# Preamp_board1.net
KiCad netlist of a schematic drawn in EAGLE
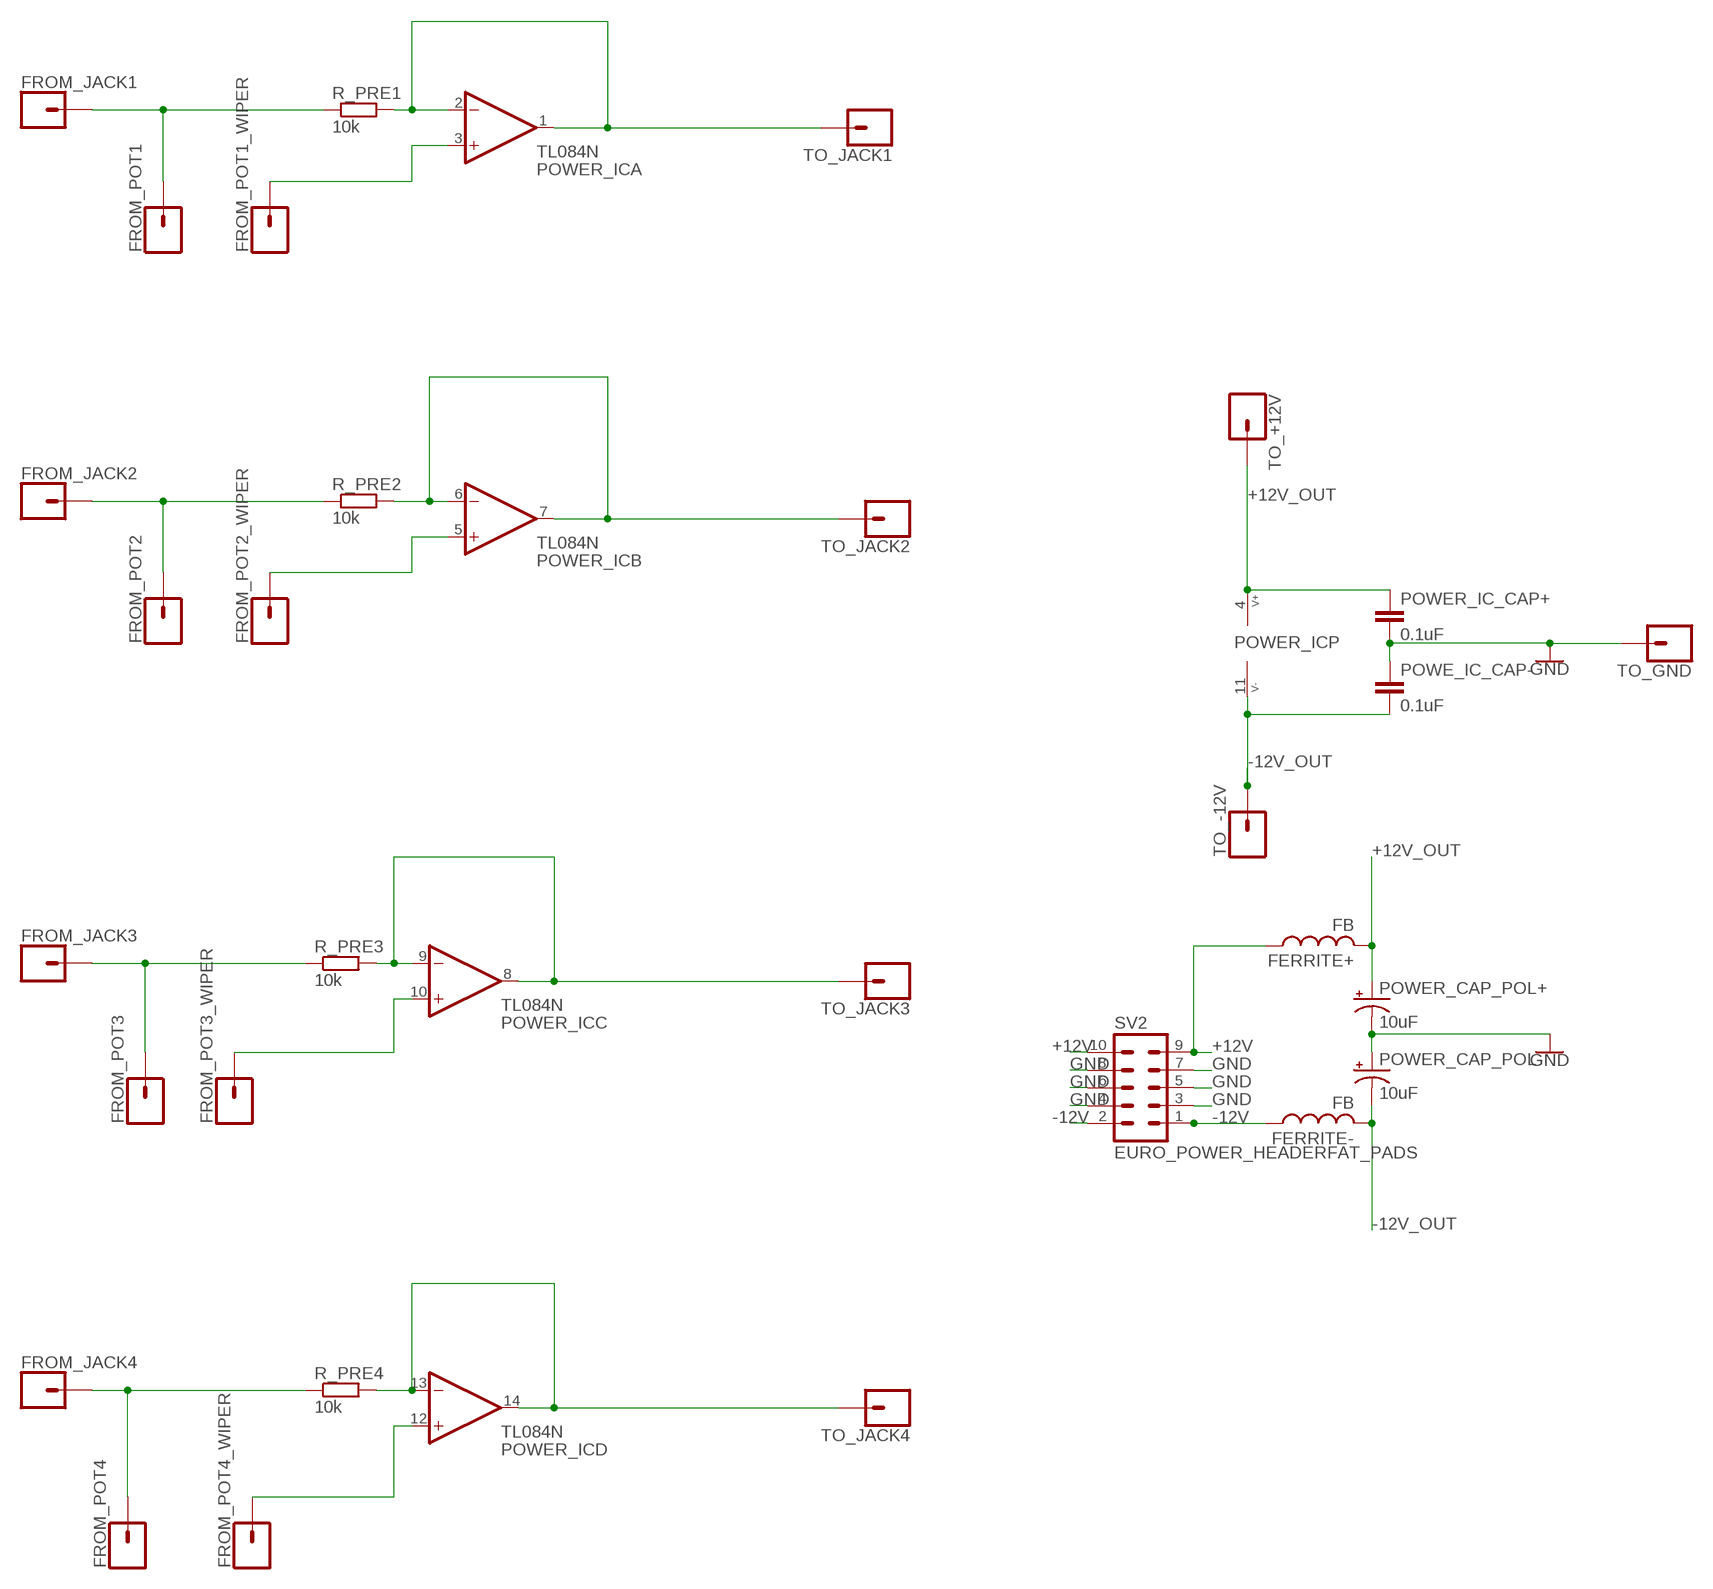
[diagram p0: schematic, sheet 1]

(export (version "E")
  (design (tool "Eeschema 10.0.6"))
  (components
    (comp (ref "FERRITE+")
      (value "FB")
      (footprint "eagle-import:FB")
      (libsource (lib "eagle-import") (part "FB"))
    )
    (comp (ref "FERRITE-")
      (value "FB")
      (footprint "eagle-import:FB")
      (libsource (lib "eagle-import") (part "FB"))
    )
    (comp (ref "FROM_JACK1")
      (value "CONN_01PTH_LONGPAD")
      (footprint "eagle-import:1X01_LONGPAD")
      (libsource (lib "eagle-import") (part "CONN_01PTH_LONGPAD"))
    )
    (comp (ref "FROM_JACK2")
      (value "CONN_01PTH_LONGPAD")
      (footprint "eagle-import:1X01_LONGPAD")
      (libsource (lib "eagle-import") (part "CONN_01PTH_LONGPAD"))
    )
    (comp (ref "FROM_JACK3")
      (value "CONN_01PTH_LONGPAD")
      (footprint "eagle-import:1X01_LONGPAD")
      (libsource (lib "eagle-import") (part "CONN_01PTH_LONGPAD"))
    )
    (comp (ref "FROM_JACK4")
      (value "CONN_01PTH_LONGPAD")
      (footprint "eagle-import:1X01_LONGPAD")
      (libsource (lib "eagle-import") (part "CONN_01PTH_LONGPAD"))
    )
    (comp (ref "FROM_POT1")
      (value "CONN_01PTH_LONGPAD")
      (footprint "eagle-import:1X01_LONGPAD")
      (libsource (lib "eagle-import") (part "CONN_01PTH_LONGPAD"))
    )
    (comp (ref "FROM_POT1_WIPER")
      (value "CONN_01PTH_LONGPAD")
      (footprint "eagle-import:1X01_LONGPAD")
      (libsource (lib "eagle-import") (part "CONN_01PTH_LONGPAD"))
    )
    (comp (ref "FROM_POT2")
      (value "CONN_01PTH_LONGPAD")
      (footprint "eagle-import:1X01_LONGPAD")
      (libsource (lib "eagle-import") (part "CONN_01PTH_LONGPAD"))
    )
    (comp (ref "FROM_POT2_WIPER")
      (value "CONN_01PTH_LONGPAD")
      (footprint "eagle-import:1X01_LONGPAD")
      (libsource (lib "eagle-import") (part "CONN_01PTH_LONGPAD"))
    )
    (comp (ref "FROM_POT3")
      (value "CONN_01PTH_LONGPAD")
      (footprint "eagle-import:1X01_LONGPAD")
      (libsource (lib "eagle-import") (part "CONN_01PTH_LONGPAD"))
    )
    (comp (ref "FROM_POT3_WIPER")
      (value "CONN_01PTH_LONGPAD")
      (footprint "eagle-import:1X01_LONGPAD")
      (libsource (lib "eagle-import") (part "CONN_01PTH_LONGPAD"))
    )
    (comp (ref "FROM_POT4")
      (value "CONN_01PTH_LONGPAD")
      (footprint "eagle-import:1X01_LONGPAD")
      (libsource (lib "eagle-import") (part "CONN_01PTH_LONGPAD"))
    )
    (comp (ref "FROM_POT4_WIPER")
      (value "CONN_01PTH_LONGPAD")
      (footprint "eagle-import:1X01_LONGPAD")
      (libsource (lib "eagle-import") (part "CONN_01PTH_LONGPAD"))
    )
    (comp (ref "POWER_CAP_POL+")
      (value "10uF")
      (footprint "eagle-import:CPOL-RADIAL-2.5MM-5MM")
      (libsource (lib "eagle-import") (part "10UF-POLAR-RADIAL-2.5MM-25V-20%"))
    )
    (comp (ref "POWER_CAP_POL-")
      (value "10uF")
      (footprint "eagle-import:CPOL-RADIAL-2.5MM-5MM")
      (libsource (lib "eagle-import") (part "10UF-POLAR-RADIAL-2.5MM-25V-20%"))
    )
    (comp (ref "POWER_IC")
      (value "TL084N")
      (footprint "eagle-import:DIL14")
      (libsource (lib "eagle-import") (part "TL084N"))
    )
    (comp (ref "POWER_IC_CAP+")
      (value "0.1uF")
      (footprint "eagle-import:CAP-PTH-SMALL-KIT")
      (libsource (lib "eagle-import") (part "0.1UF-KIT-EZ-50V-20%"))
    )
    (comp (ref "POWE_IC_CAP-")
      (value "0.1uF")
      (footprint "eagle-import:CAP-PTH-SMALL-KIT")
      (libsource (lib "eagle-import") (part "0.1UF-KIT-EZ-50V-20%"))
    )
    (comp (ref "R_PRE1")
      (value "10k")
      (footprint "eagle-import:7MM_RESISTOR")
      (libsource (lib "eagle-import") (part "RESISTOR7MM"))
    )
    (comp (ref "R_PRE2")
      (value "10k")
      (footprint "eagle-import:7MM_RESISTOR")
      (libsource (lib "eagle-import") (part "RESISTOR7MM"))
    )
    (comp (ref "R_PRE3")
      (value "10k")
      (footprint "eagle-import:7MM_RESISTOR")
      (libsource (lib "eagle-import") (part "RESISTOR7MM"))
    )
    (comp (ref "R_PRE4")
      (value "10k")
      (footprint "eagle-import:7MM_RESISTOR")
      (libsource (lib "eagle-import") (part "RESISTOR7MM"))
    )
    (comp (ref "SV2")
      (value "EURO_POWER_HEADERFAT_PADS")
      (footprint "eagle-import:EURO_PWR_HEADER_FAT")
      (libsource (lib "eagle-import") (part "EURO_POWER_HEADERFAT_PADS"))
    )
    (comp (ref "TO_+12V")
      (value "CONN_01PTH_LONGPAD")
      (footprint "eagle-import:1X01_LONGPAD")
      (libsource (lib "eagle-import") (part "CONN_01PTH_LONGPAD"))
    )
    (comp (ref "TO_-12V")
      (value "CONN_01PTH_LONGPAD")
      (footprint "eagle-import:1X01_LONGPAD")
      (libsource (lib "eagle-import") (part "CONN_01PTH_LONGPAD"))
    )
    (comp (ref "TO_GND")
      (value "CONN_01PTH_LONGPAD")
      (footprint "eagle-import:1X01_LONGPAD")
      (libsource (lib "eagle-import") (part "CONN_01PTH_LONGPAD"))
    )
    (comp (ref "TO_JACK1")
      (value "CONN_01PTH_LONGPAD")
      (footprint "eagle-import:1X01_LONGPAD")
      (libsource (lib "eagle-import") (part "CONN_01PTH_LONGPAD"))
    )
    (comp (ref "TO_JACK2")
      (value "CONN_01PTH_LONGPAD")
      (footprint "eagle-import:1X01_LONGPAD")
      (libsource (lib "eagle-import") (part "CONN_01PTH_LONGPAD"))
    )
    (comp (ref "TO_JACK3")
      (value "CONN_01PTH_LONGPAD")
      (footprint "eagle-import:1X01_LONGPAD")
      (libsource (lib "eagle-import") (part "CONN_01PTH_LONGPAD"))
    )
    (comp (ref "TO_JACK4")
      (value "CONN_01PTH_LONGPAD")
      (footprint "eagle-import:1X01_LONGPAD")
      (libsource (lib "eagle-import") (part "CONN_01PTH_LONGPAD"))
    )
  )
  (nets
    (net (code "1") (name "/+12V") (class "Default")
      (node (ref "FERRITE+") (pin "P$1") (pinfunction "1_P$1") (pintype "passive"))
      (node (ref "SV2") (pin "10") (pinfunction "10_10") (pintype "passive"))
      (node (ref "SV2") (pin "9") (pinfunction "9_9") (pintype "passive"))
    )
    (net (code "2") (name "/+12V_OUT") (class "Default")
      (node (ref "FERRITE+") (pin "P$2") (pinfunction "2_P$2") (pintype "passive"))
      (node (ref "POWER_CAP_POL+") (pin "1") (pinfunction "+_1") (pintype "passive"))
      (node (ref "POWER_IC") (pin "4") (pinfunction "V+_4") (pintype "power_in"))
      (node (ref "POWER_IC_CAP+") (pin "1") (pinfunction "1_1") (pintype "passive"))
      (node (ref "TO_+12V") (pin "1") (pinfunction "1_1") (pintype "passive"))
    )
    (net (code "3") (name "/-12V") (class "Default")
      (node (ref "FERRITE-") (pin "P$1") (pinfunction "1_P$1") (pintype "passive"))
      (node (ref "SV2") (pin "1") (pinfunction "1_1") (pintype "passive"))
      (node (ref "SV2") (pin "2") (pinfunction "2_2") (pintype "passive"))
    )
    (net (code "4") (name "/-12V_OUT") (class "Default")
      (node (ref "FERRITE-") (pin "P$2") (pinfunction "2_P$2") (pintype "passive"))
      (node (ref "POWER_CAP_POL-") (pin "2") (pinfunction "-_2") (pintype "passive"))
      (node (ref "POWER_IC") (pin "11") (pinfunction "V-_11") (pintype "power_in"))
      (node (ref "POWE_IC_CAP-") (pin "2") (pinfunction "2_2") (pintype "passive"))
      (node (ref "TO_-12V") (pin "1") (pinfunction "1_1") (pintype "passive"))
    )
    (net (code "5") (name "GND") (class "Default")
      (node (ref "POWER_CAP_POL+") (pin "2") (pinfunction "-_2") (pintype "passive"))
      (node (ref "POWER_CAP_POL-") (pin "1") (pinfunction "+_1") (pintype "passive"))
      (node (ref "POWER_IC_CAP+") (pin "2") (pinfunction "2_2") (pintype "passive"))
      (node (ref "POWE_IC_CAP-") (pin "1") (pinfunction "1_1") (pintype "passive"))
      (node (ref "SV2") (pin "3") (pinfunction "3_3") (pintype "passive"))
      (node (ref "SV2") (pin "4") (pinfunction "4_4") (pintype "passive"))
      (node (ref "SV2") (pin "5") (pinfunction "5_5") (pintype "passive"))
      (node (ref "SV2") (pin "6") (pinfunction "6_6") (pintype "passive"))
      (node (ref "SV2") (pin "7") (pinfunction "7_7") (pintype "passive"))
      (node (ref "SV2") (pin "8") (pinfunction "8_8") (pintype "passive"))
      (node (ref "TO_GND") (pin "1") (pinfunction "1_1") (pintype "passive"))
    )
    (net (code "6") (name "Net-(FROM_JACK1-Pad1)") (class "Default")
      (node (ref "FROM_JACK1") (pin "1") (pinfunction "1_1") (pintype "passive"))
      (node (ref "FROM_POT1") (pin "1") (pinfunction "1_1") (pintype "passive"))
      (node (ref "R_PRE1") (pin "1") (pinfunction "1_1") (pintype "passive"))
    )
    (net (code "7") (name "Net-(FROM_JACK2-Pad1)") (class "Default")
      (node (ref "FROM_JACK2") (pin "1") (pinfunction "1_1") (pintype "passive"))
      (node (ref "FROM_POT2") (pin "1") (pinfunction "1_1") (pintype "passive"))
      (node (ref "R_PRE2") (pin "1") (pinfunction "1_1") (pintype "passive"))
    )
    (net (code "8") (name "Net-(FROM_JACK3-Pad1)") (class "Default")
      (node (ref "FROM_JACK3") (pin "1") (pinfunction "1_1") (pintype "passive"))
      (node (ref "FROM_POT3") (pin "1") (pinfunction "1_1") (pintype "passive"))
      (node (ref "R_PRE3") (pin "1") (pinfunction "1_1") (pintype "passive"))
    )
    (net (code "9") (name "Net-(FROM_JACK4-Pad1)") (class "Default")
      (node (ref "FROM_JACK4") (pin "1") (pinfunction "1_1") (pintype "passive"))
      (node (ref "FROM_POT4") (pin "1") (pinfunction "1_1") (pintype "passive"))
      (node (ref "R_PRE4") (pin "1") (pinfunction "1_1") (pintype "passive"))
    )
    (net (code "10") (name "Net-(POWER_ICA-+IN)") (class "Default")
      (node (ref "FROM_POT1_WIPER") (pin "1") (pinfunction "1_1") (pintype "passive"))
      (node (ref "POWER_IC") (pin "3") (pinfunction "+IN_3") (pintype "input"))
    )
    (net (code "11") (name "Net-(POWER_ICA--IN)") (class "Default")
      (node (ref "POWER_IC") (pin "1") (pinfunction "OUT_1") (pintype "output"))
      (node (ref "POWER_IC") (pin "2") (pinfunction "-IN_2") (pintype "input"))
      (node (ref "R_PRE1") (pin "2") (pinfunction "2_2") (pintype "passive"))
      (node (ref "TO_JACK1") (pin "1") (pinfunction "1_1") (pintype "passive"))
    )
    (net (code "12") (name "Net-(POWER_ICB-+IN)") (class "Default")
      (node (ref "FROM_POT2_WIPER") (pin "1") (pinfunction "1_1") (pintype "passive"))
      (node (ref "POWER_IC") (pin "5") (pinfunction "+IN_5") (pintype "input"))
    )
    (net (code "13") (name "Net-(POWER_ICB--IN)") (class "Default")
      (node (ref "POWER_IC") (pin "6") (pinfunction "-IN_6") (pintype "input"))
      (node (ref "POWER_IC") (pin "7") (pinfunction "OUT_7") (pintype "output"))
      (node (ref "R_PRE2") (pin "2") (pinfunction "2_2") (pintype "passive"))
      (node (ref "TO_JACK2") (pin "1") (pinfunction "1_1") (pintype "passive"))
    )
    (net (code "14") (name "Net-(POWER_ICC-+IN)") (class "Default")
      (node (ref "FROM_POT3_WIPER") (pin "1") (pinfunction "1_1") (pintype "passive"))
      (node (ref "POWER_IC") (pin "10") (pinfunction "+IN_10") (pintype "input"))
    )
    (net (code "15") (name "Net-(POWER_ICC--IN)") (class "Default")
      (node (ref "POWER_IC") (pin "8") (pinfunction "OUT_8") (pintype "output"))
      (node (ref "POWER_IC") (pin "9") (pinfunction "-IN_9") (pintype "input"))
      (node (ref "R_PRE3") (pin "2") (pinfunction "2_2") (pintype "passive"))
      (node (ref "TO_JACK3") (pin "1") (pinfunction "1_1") (pintype "passive"))
    )
    (net (code "16") (name "Net-(POWER_ICD-+IN)") (class "Default")
      (node (ref "FROM_POT4_WIPER") (pin "1") (pinfunction "1_1") (pintype "passive"))
      (node (ref "POWER_IC") (pin "12") (pinfunction "+IN_12") (pintype "input"))
    )
    (net (code "17") (name "Net-(POWER_ICD--IN)") (class "Default")
      (node (ref "POWER_IC") (pin "13") (pinfunction "-IN_13") (pintype "input"))
      (node (ref "POWER_IC") (pin "14") (pinfunction "OUT_14") (pintype "output"))
      (node (ref "R_PRE4") (pin "2") (pinfunction "2_2") (pintype "passive"))
      (node (ref "TO_JACK4") (pin "1") (pinfunction "1_1") (pintype "passive"))
    )
  )
)
